# UVLO_MODULE_TOP.net
KiCad netlist of a schematic drawn in Altium Designer
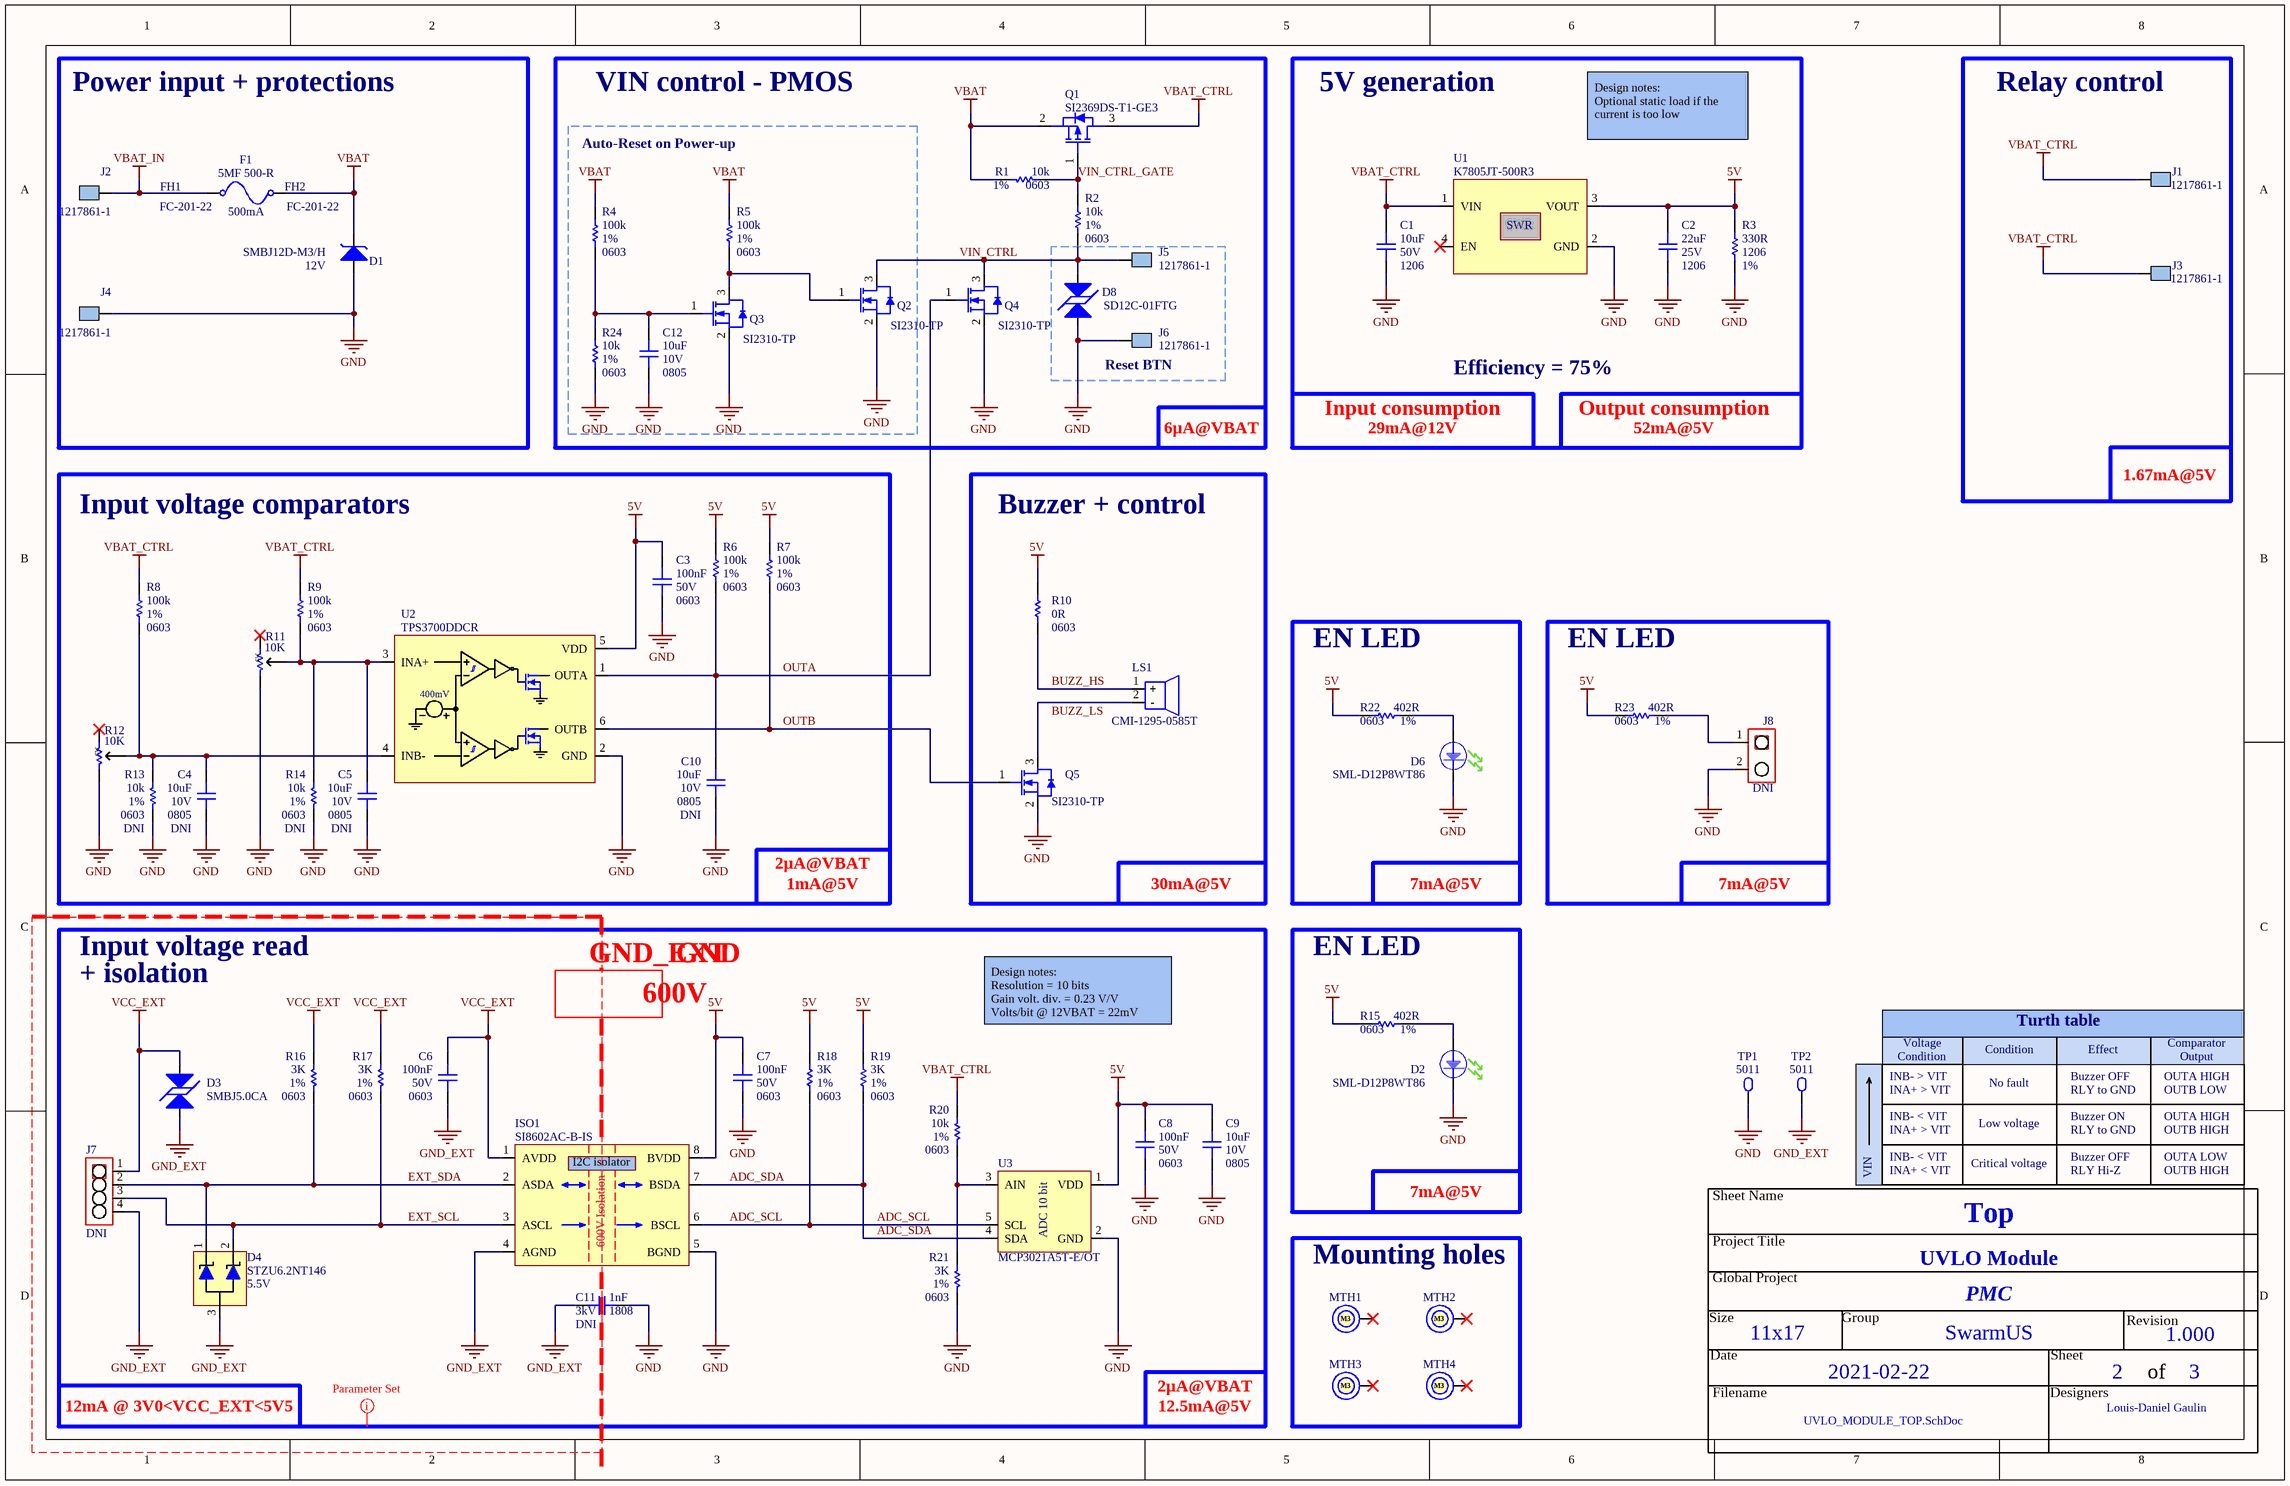
[diagram p0: UVLO_MODULE_TOP.SchDoc]

(export (version "E")
  (design (tool "Eeschema 10.0.6"))
  (components
    (comp (ref "C1")
      (value "10uF")
      (footprint "CAP_CER_1206")
      (description "CAP - CER 10UF 10% 50V X5R - 1206")
      (fields
        (field (name "TOLERANCE") "10%")
        (field (name "PACKAGE") "1206")
        (field (name "VOLTAGE RATING") "50V")
        (field (name "Comment") "GRT31CR61H106KE01L")
        (field (name "CREATEDBY/DATE") "Nicolas Roy - 2018/12/19")
        (field (name "VERIFIEDBY") "Nicolas V. (2019-01-22)")
      )
      (libsource (lib "GRAMS_MASTER_LIB") (part "CAP_CER_GRT31CR61H106KE01L"))
    )
    (comp (ref "C2")
      (value "22uF")
      (footprint "CAP_CER_1206")
      (description "CAP - CER 22uF 10% 25V X5R - 1206")
      (fields
        (field (name "TOLERANCE") "10%")
        (field (name "PACKAGE") "1206")
        (field (name "VOLTAGE RATING") "25V")
        (field (name "Comment") "CL31A226KAHNNNE")
        (field (name "CREATEDBY/DATE") "Philippe Arsenault/21 Janvier 2020")
        (field (name "VERIFIEDBY") "C.Paulin - 28/01/2020")
      )
      (libsource (lib "GRAMS_MASTER_LIB") (part "CAP_CER_CL31A226KAHNNNE"))
    )
    (comp (ref "C3")
      (value "100nF")
      (footprint "CAP_CER_0603")
      (description "CAP - CER 100nF 50V X7R - 0603")
      (fields
        (field (name "TOLERANCE") "10%")
        (field (name "PACKAGE") "0603")
        (field (name "VOLTAGE RATING") "50V")
        (field (name "Comment") "CC0603KRX7R9BB104")
        (field (name "CREATEDBY/DATE") "Louis-Daniel Gaulin / 25-02-2021")
        (field (name "VERIFIEDBY") "Hubert Dube - 26/02/2021")
      )
      (libsource (lib "SWARMUS_LIB") (part "CAP_CER_CC0603KRX7R9BB104"))
    )
    (comp (ref "C4")
      (value "10uF")
      (footprint "CAP_CER_0805")
      (description "CAP - CER 10UF 10% 10V X5R - 0805")
      (fields
        (field (name "TOLERANCE") "10%")
        (field (name "ASSEMBLY NOTE") "DNI")
        (field (name "PACKAGE") "0805")
        (field (name "VOLTAGE RATING") "10V")
        (field (name "Comment") "LMK212BJ106KG-T")
        (field (name "CREATEDBY/DATE") "Caroline Paulin / 25 juillet 2018")
        (field (name "VERIFIEDBY") "Nicolas V. (2019-01-22)")
      )
      (libsource (lib "GRAMS_MASTER_LIB") (part "CAP_CER_LMK212BJ106KG-T"))
    )
    (comp (ref "C5")
      (value "10uF")
      (footprint "CAP_CER_0805")
      (description "CAP - CER 10UF 10% 10V X5R - 0805")
      (fields
        (field (name "TOLERANCE") "10%")
        (field (name "ASSEMBLY NOTE") "DNI")
        (field (name "PACKAGE") "0805")
        (field (name "VOLTAGE RATING") "10V")
        (field (name "Comment") "LMK212BJ106KG-T")
        (field (name "CREATEDBY/DATE") "Caroline Paulin / 25 juillet 2018")
        (field (name "VERIFIEDBY") "Nicolas V. (2019-01-22)")
      )
      (libsource (lib "GRAMS_MASTER_LIB") (part "CAP_CER_LMK212BJ106KG-T"))
    )
    (comp (ref "C6")
      (value "100nF")
      (footprint "CAP_CER_0603")
      (description "CAP - CER 100nF 50V X7R - 0603")
      (fields
        (field (name "TOLERANCE") "10%")
        (field (name "PACKAGE") "0603")
        (field (name "VOLTAGE RATING") "50V")
        (field (name "Comment") "CC0603KRX7R9BB104")
        (field (name "CREATEDBY/DATE") "Louis-Daniel Gaulin / 25-02-2021")
        (field (name "VERIFIEDBY") "Hubert Dube - 26/02/2021")
      )
      (libsource (lib "SWARMUS_LIB") (part "CAP_CER_CC0603KRX7R9BB104"))
    )
    (comp (ref "C7")
      (value "100nF")
      (footprint "CAP_CER_0603")
      (description "CAP - CER 100nF 50V X7R - 0603")
      (fields
        (field (name "TOLERANCE") "10%")
        (field (name "PACKAGE") "0603")
        (field (name "VOLTAGE RATING") "50V")
        (field (name "Comment") "CC0603KRX7R9BB104")
        (field (name "CREATEDBY/DATE") "Louis-Daniel Gaulin / 25-02-2021")
        (field (name "VERIFIEDBY") "Hubert Dube - 26/02/2021")
      )
      (libsource (lib "SWARMUS_LIB") (part "CAP_CER_CC0603KRX7R9BB104"))
    )
    (comp (ref "C8")
      (value "100nF")
      (footprint "CAP_CER_0603")
      (description "CAP - CER 100nF 50V X7R - 0603")
      (fields
        (field (name "TOLERANCE") "10%")
        (field (name "PACKAGE") "0603")
        (field (name "VOLTAGE RATING") "50V")
        (field (name "Comment") "CC0603KRX7R9BB104")
        (field (name "CREATEDBY/DATE") "Louis-Daniel Gaulin / 25-02-2021")
        (field (name "VERIFIEDBY") "Hubert Dube - 26/02/2021")
      )
      (libsource (lib "SWARMUS_LIB") (part "CAP_CER_CC0603KRX7R9BB104"))
    )
    (comp (ref "C9")
      (value "10uF")
      (footprint "CAP_CER_0805")
      (description "CAP - CER 10UF 10% 10V X5R - 0805")
      (fields
        (field (name "TOLERANCE") "10%")
        (field (name "PACKAGE") "0805")
        (field (name "VOLTAGE RATING") "10V")
        (field (name "Comment") "LMK212BJ106KG-T")
        (field (name "CREATEDBY/DATE") "Caroline Paulin / 25 juillet 2018")
        (field (name "VERIFIEDBY") "Nicolas V. (2019-01-22)")
      )
      (libsource (lib "GRAMS_MASTER_LIB") (part "CAP_CER_LMK212BJ106KG-T"))
    )
    (comp (ref "C10")
      (value "10uF")
      (footprint "CAP_CER_0805")
      (description "CAP - CER 10UF 10% 10V X5R - 0805")
      (fields
        (field (name "TOLERANCE") "10%")
        (field (name "ASSEMBLY NOTE") "DNI")
        (field (name "PACKAGE") "0805")
        (field (name "VOLTAGE RATING") "10V")
        (field (name "Comment") "LMK212BJ106KG-T")
        (field (name "CREATEDBY/DATE") "Caroline Paulin / 25 juillet 2018")
        (field (name "VERIFIEDBY") "Nicolas V. (2019-01-22)")
      )
      (libsource (lib "GRAMS_MASTER_LIB") (part "CAP_CER_LMK212BJ106KG-T"))
    )
    (comp (ref "C11")
      (value "1nF")
      (footprint "CAP_CER_1808")
      (description "CAP - CER 1nF 10% 3kV X7R - 1808")
      (fields
        (field (name "TOLERANCE") "10%")
        (field (name "ASSEMBLY NOTE") "DNI")
        (field (name "PACKAGE") "1808")
        (field (name "VOLTAGE RATING") "3kV")
        (field (name "Comment") "1808HC102KAT1A")
        (field (name "CREATEDBY/DATE") "Joel Lemay 2018-08-29")
        (field (name "VERIFIEDBY") "Caroline Paulin - 7 sept 2018")
      )
      (libsource (lib "GRAMS_MASTER_LIB") (part "CAP_CER_1808HC102KAT1A"))
    )
    (comp (ref "C12")
      (value "10uF")
      (footprint "CAP_CER_0805")
      (description "CAP - CER 10UF 10% 10V X5R - 0805")
      (fields
        (field (name "TOLERANCE") "10%")
        (field (name "PACKAGE") "0805")
        (field (name "VOLTAGE RATING") "10V")
        (field (name "Comment") "LMK212BJ106KG-T")
        (field (name "CREATEDBY/DATE") "Caroline Paulin / 25 juillet 2018")
        (field (name "VERIFIEDBY") "Nicolas V. (2019-01-22)")
      )
      (libsource (lib "GRAMS_MASTER_LIB") (part "CAP_CER_LMK212BJ106KG-T"))
    )
    (comp (ref "D1")
      (value "SMBJ12D-M3/H")
      (footprint "TVS_SMBJ12D-M3/H")
      (description "TVS - DIODE 12V 19.6V - DO-214AA")
      (fields
        (field (name "ALTIUM_VALUE") "12V")
        (field (name "CREATEDBY/DATE") "Joel Lemay 2019-04-17")
        (field (name "VERIFIEDBY") "C.Paulin 6/02/2020")
      )
      (libsource (lib "GRAMS_MASTER_LIB") (part "TVS_SMBJ12D-M3/H"))
    )
    (comp (ref "D2")
      (value "SML-D12P8WT86")
      (footprint "LED_SML-D12P8WT86")
      (description "LED - GREEN DIFFUSED 0603 SMD - 0603")
      (fields
        (field (name "CREATEDBY/DATE") "Keven Deslandes - 2018/11/21")
        (field (name "VERIFIEDBY") "Caroline Paulin - 13 février 2019")
      )
      (libsource (lib "GRAMS_MASTER_LIB") (part "LED_SML-D12P8WT86"))
    )
    (comp (ref "D3")
      (value "SMBJ5.0CA")
      (footprint "TVS_PWR_SMBJ5.0CA")
      (description "TVS - BIDIR 5V 9.2V 600W - DO214AA")
      (fields
        (field (name "CREATEDBY/DATE") "Jonathan Bouchard - 2019-03-22")
        (field (name "VERIFIEDBY") "Nicolas V. (2019-05-06)")
      )
      (libsource (lib "GRAMS_MASTER_LIB") (part "TVS_PWR_SMBJ5.0CA"))
    )
    (comp (ref "D4")
      (value "STZU6.2NT146")
      (footprint "TVS_DATA_STZU6.2NT146")
      (description "TVS - TVS DIODE 5.5V 5.9V - SOT-23-3")
      (fields
        (field (name "VOLTAGE RATING") "5.5V")
        (field (name "CREATEDBY/DATE") "Louis-Daniel Gaulin / 02-03-2021")
        (field (name "VERIFIEDBY") "Philippe Arsenault / 02-03-2021")
      )
      (libsource (lib "SWARMUS_LIB") (part "TVS_DATA_STZU6.2NT146"))
    )
    (comp (ref "D6")
      (value "SML-D12P8WT86")
      (footprint "LED_SML-D12P8WT86")
      (description "LED - GREEN DIFFUSED 0603 SMD - 0603")
      (fields
        (field (name "CREATEDBY/DATE") "Keven Deslandes - 2018/11/21")
        (field (name "VERIFIEDBY") "Caroline Paulin - 13 février 2019")
      )
      (libsource (lib "GRAMS_MASTER_LIB") (part "LED_SML-D12P8WT86"))
    )
    (comp (ref "D8")
      (value "SD12C-01FTG")
      (footprint "TVS_DATA_SD12C-01FTG")
      (description "TVS - BIDIR 12V 450W - SOD-323")
      (fields
        (field (name "CREATEDBY/DATE") "O.D.Frenette - 2020-09-01")
        (field (name "VERIFIEDBY") "C.Paulin - 2020-09-09")
      )
      (libsource (lib "GRAMS_MASTER_LIB") (part "TVS_DATA_SD12C-01FTG"))
    )
    (comp (ref "F1")
      (value "5MF 500-R")
      (footprint "FUS_5MF 500-R")
      (description "FUS - CARTRIDGE GLASS 500mA 250VAC/125VDC - 5X20mm")
      (fields
        (field (name "CURRENT RATING") "500mA")
        (field (name "CREATEDBY/DATE") "Louis-Daniel Gaulin")
        (field (name "VERIFIEDBY") "Hubert Dube - 26/02/2021")
      )
      (libsource (lib "SWARMUS_LIB") (part "FUS_5MF 500-R"))
    )
    (comp (ref "FH1")
      (value "FC-201-22")
      (footprint "FHO_FC-201-22")
      (description "FHO - FUSE CLIP 5mm CARTRIDGE 10A PCB - 2-TH")
      (fields
        (field (name "CREATEDBY/DATE") "Louis-Daniel Gaulin / 26-02-2021")
        (field (name "VERIFIEDBY") "Hubert Dube - 26/02/2021")
      )
      (libsource (lib "SWARMUS_LIB") (part "FHO_FC-201-22"))
    )
    (comp (ref "FH2")
      (value "FC-201-22")
      (footprint "FHO_FC-201-22")
      (description "FHO - FUSE CLIP 5mm CARTRIDGE 10A PCB - 2-TH")
      (fields
        (field (name "CREATEDBY/DATE") "Louis-Daniel Gaulin / 26-02-2021")
        (field (name "VERIFIEDBY") "Hubert Dube - 26/02/2021")
      )
      (libsource (lib "SWARMUS_LIB") (part "FHO_FC-201-22"))
    )
    (comp (ref "ISO1")
      (value "SI8602AC-B-IS")
      (footprint "ISO_SI8602AC-B-IS")
      (description "ISO - DGTL ISO 600V 2CH I2C  - 8-SOIC")
      (fields
        (field (name "CREATEDBY/DATE") "Louis-Daniel Gaulin / 25-02-2021")
        (field (name "VERIFIEDBY") "Hubert Dube - 26/02/2021")
      )
      (libsource (lib "SWARMUS_LIB") (part "ISO_SI8602AC-B-IS"))
    )
    (comp (ref "J1")
      (value "1217861-1")
      (footprint "CON_1217861-1")
      (description "CON - Quick connect tab - TH")
      (fields
        (field (name "CREATEDBY/DATE") "Louis-Daniel Gaulin / 24-02-2021")
        (field (name "VERIFIEDBY") "Hubert Dube - 26/02/2021")
      )
      (libsource (lib "") (part "CON_1217861-1_1"))
    )
    (comp (ref "J2")
      (value "1217861-1")
      (footprint "CON_1217861-1")
      (description "CON - Quick connect tab - TH")
      (fields
        (field (name "CREATEDBY/DATE") "Louis-Daniel Gaulin / 24-02-2021")
        (field (name "VERIFIEDBY") "Hubert Dube - 26/02/2021")
      )
      (libsource (lib "SWARMUS_LIB") (part "CON_1217861-1"))
    )
    (comp (ref "J3")
      (value "1217861-1")
      (footprint "CON_1217861-1")
      (description "CON - Quick connect tab - TH")
      (fields
        (field (name "CREATEDBY/DATE") "Louis-Daniel Gaulin / 24-02-2021")
        (field (name "VERIFIEDBY") "Hubert Dube - 26/02/2021")
      )
      (libsource (lib "") (part "CON_1217861-1_1"))
    )
    (comp (ref "J4")
      (value "1217861-1")
      (footprint "CON_1217861-1")
      (description "CON - Quick connect tab - TH")
      (fields
        (field (name "CREATEDBY/DATE") "Louis-Daniel Gaulin / 24-02-2021")
        (field (name "VERIFIEDBY") "Hubert Dube - 26/02/2021")
      )
      (libsource (lib "SWARMUS_LIB") (part "CON_1217861-1"))
    )
    (comp (ref "J5")
      (value "1217861-1")
      (footprint "CON_1217861-1")
      (description "CON - Quick connect tab - TH")
      (fields
        (field (name "CREATEDBY/DATE") "Louis-Daniel Gaulin / 24-02-2021")
        (field (name "VERIFIEDBY") "Hubert Dube - 26/02/2021")
      )
      (libsource (lib "") (part "CON_1217861-1_2"))
    )
    (comp (ref "J6")
      (value "1217861-1")
      (footprint "CON_1217861-1")
      (description "CON - Quick connect tab - TH")
      (fields
        (field (name "CREATEDBY/DATE") "Louis-Daniel Gaulin / 24-02-2021")
        (field (name "VERIFIEDBY") "Hubert Dube - 26/02/2021")
      )
      (libsource (lib "") (part "CON_1217861-1_2"))
    )
    (comp (ref "J7")
      (value "CON_HDR_1X4")
      (footprint "CON_HDR_1X4")
      (description "CON - Header 1X4 pins, 100Mils - TH-4")
      (fields
        (field (name "ASSEMBLY NOTE") "DNI")
        (field (name "CREATEDBY/DATE") "Nicolas V (2020-02-24)")
        (field (name "VERIFIEDBY") "Nicolas V (2020-02-24)")
      )
      (libsource (lib "GRAMS_MASTER_LIB") (part "CON_HDR_1X4"))
    )
    (comp (ref "J8")
      (value "CON_HDR_1X2")
      (footprint "CON_HDR_1X2")
      (description "CON - Header 1x2 pins 100 mil -TH")
      (fields
        (field (name "ASSEMBLY NOTE") "DNI")
        (field (name "CREATEDBY/DATE") "Nicolas Roy/2 dec 2016")
        (field (name "VERIFIEDBY") "Caroline Paulin / 10 juillet 2018")
      )
      (libsource (lib "GRAMS_MASTER_LIB") (part "CON_HDR_1X2"))
    )
    (comp (ref "LS1")
      (value "CMI-1295-0585T")
      (footprint "UND_SPK_CMI-1295-0585T")
      (description "LS - Buzzer indicator 5V 30mA 2.3kHz 85dB - TH")
      (fields
        (field (name "CREATEDBY/DATE") "Louis-Daniel Gaulin / 24-02-2021")
        (field (name "VERIFIEDBY") "Hubert Dube - 26/02/2021")
      )
      (libsource (lib "SWARMUS_LIB") (part "UND_LS_CMI-1295-0585T"))
    )
    (comp (ref "MTH1")
      (value "M3")
      (footprint "MTH_M3")
      (description "MTH - MOUNTING HOLE M3 PLATED - M3")
      (fields
        (field (name "CREATEDBY/DATE") "Jonathan Bouchard 2018-07-23")
        (field (name "VERIFIEDBY") "Arnaud Samson 23-07-18")
      )
      (libsource (lib "GRAMS_MASTER_LIB") (part "MTH_M3"))
    )
    (comp (ref "MTH2")
      (value "M3")
      (footprint "MTH_M3")
      (description "MTH - MOUNTING HOLE M3 PLATED - M3")
      (fields
        (field (name "CREATEDBY/DATE") "Jonathan Bouchard 2018-07-23")
        (field (name "VERIFIEDBY") "Arnaud Samson 23-07-18")
      )
      (libsource (lib "GRAMS_MASTER_LIB") (part "MTH_M3"))
    )
    (comp (ref "MTH3")
      (value "M3")
      (footprint "MTH_M3")
      (description "MTH - MOUNTING HOLE M3 PLATED - M3")
      (fields
        (field (name "CREATEDBY/DATE") "Jonathan Bouchard 2018-07-23")
        (field (name "VERIFIEDBY") "Arnaud Samson 23-07-18")
      )
      (libsource (lib "GRAMS_MASTER_LIB") (part "MTH_M3"))
    )
    (comp (ref "MTH4")
      (value "M3")
      (footprint "MTH_M3")
      (description "MTH - MOUNTING HOLE M3 PLATED - M3")
      (fields
        (field (name "CREATEDBY/DATE") "Jonathan Bouchard 2018-07-23")
        (field (name "VERIFIEDBY") "Arnaud Samson 23-07-18")
      )
      (libsource (lib "GRAMS_MASTER_LIB") (part "MTH_M3"))
    )
    (comp (ref "Q1")
      (value "SI2369DS-T1-GE3")
      (footprint "TRX_PMOS_SI2369DS-T1-GE3")
      (description "TRX - PMOS 30V 7.6A - SOT−23")
      (fields
        (field (name "CREATEDBY/DATE") "Louis-Daniel Gaulin / 30-07-2020")
        (field (name "VERIFIEDBY") "Philippe Arsenault/2020-11-06")
      )
      (libsource (lib "SWARMUS_LIB") (part "TRX_PMOS_SI2369DS-T1-GE3"))
    )
    (comp (ref "Q2")
      (value "SI2310-TP")
      (footprint "TRX_NMOS_SI2310-TP")
      (description "TRX - MOSFET N-CH 60V 3A - SOT-23")
      (fields
        (field (name "CREATEDBY/DATE") "Louis-Daniel Gaulin / 20-02-2020")
        (field (name "VERIFIEDBY") "C.Paulin - 21/02/2020")
      )
      (libsource (lib "GRAMS_MASTER_LIB") (part "TRX_NMOS_SI2310-TP"))
    )
    (comp (ref "Q3")
      (value "SI2310-TP")
      (footprint "TRX_NMOS_SI2310-TP")
      (description "TRX - MOSFET N-CH 60V 3A - SOT-23")
      (fields
        (field (name "CREATEDBY/DATE") "Louis-Daniel Gaulin / 20-02-2020")
        (field (name "VERIFIEDBY") "C.Paulin - 21/02/2020")
      )
      (libsource (lib "GRAMS_MASTER_LIB") (part "TRX_NMOS_SI2310-TP"))
    )
    (comp (ref "Q4")
      (value "SI2310-TP")
      (footprint "TRX_NMOS_SI2310-TP")
      (description "TRX - MOSFET N-CH 60V 3A - SOT-23")
      (fields
        (field (name "CREATEDBY/DATE") "Louis-Daniel Gaulin / 20-02-2020")
        (field (name "VERIFIEDBY") "C.Paulin - 21/02/2020")
      )
      (libsource (lib "GRAMS_MASTER_LIB") (part "TRX_NMOS_SI2310-TP"))
    )
    (comp (ref "Q5")
      (value "SI2310-TP")
      (footprint "TRX_NMOS_SI2310-TP")
      (description "TRX - MOSFET N-CH 60V 3A - SOT-23")
      (fields
        (field (name "CREATEDBY/DATE") "Louis-Daniel Gaulin / 20-02-2020")
        (field (name "VERIFIEDBY") "C.Paulin - 21/02/2020")
      )
      (libsource (lib "GRAMS_MASTER_LIB") (part "TRX_NMOS_SI2310-TP"))
    )
    (comp (ref "R1")
      (value "10k")
      (footprint "RES_0603")
      (description "RES - 10k 1% 1/10W - 0603")
      (fields
        (field (name "TOLERANCE") "1%")
        (field (name "PACKAGE") "0603")
        (field (name "Comment") "RC0603FR-0710KL")
        (field (name "CREATEDBY/DATE") "Louis-Daniel Gaulin / 24-02-2021")
        (field (name "VERIFIEDBY") "Hubert Dube - 26/02/2021")
      )
      (libsource (lib "SWARMUS_LIB") (part "RES_RC0603FR-0710KL"))
    )
    (comp (ref "R2")
      (value "10k")
      (footprint "RES_0603")
      (description "RES - 10k 1% 1/10W - 0603")
      (fields
        (field (name "TOLERANCE") "1%")
        (field (name "PACKAGE") "0603")
        (field (name "Comment") "RC0603FR-0710KL")
        (field (name "CREATEDBY/DATE") "Louis-Daniel Gaulin / 24-02-2021")
        (field (name "VERIFIEDBY") "Hubert Dube - 26/02/2021")
      )
      (libsource (lib "SWARMUS_LIB") (part "RES_RC0603FR-0710KL"))
    )
    (comp (ref "R3")
      (value "330R")
      (footprint "RES_1206")
      (description "RES - 330 OHM 1% 1/4W - 1206")
      (fields
        (field (name "TOLERANCE") "1%")
        (field (name "PACKAGE") "1206")
        (field (name "Comment") "RC1206FR-07330RL")
        (field (name "CREATEDBY/DATE") "Nicolas V. (2019-11-19)")
        (field (name "VERIFIEDBY") "Nicolas V. (2019-11-19)")
      )
      (libsource (lib "GRAMS_MASTER_LIB") (part "RES_RC1206FR-07330RL"))
    )
    (comp (ref "R4")
      (value "100k")
      (footprint "RES_0603")
      (description "RES - 100k 1% 1/10W - 0603")
      (fields
        (field (name "TOLERANCE") "1%")
        (field (name "PACKAGE") "0603")
        (field (name "Comment") "RC0603FR-07100KL")
        (field (name "CREATEDBY/DATE") "Louis-Daniel Gaulin / 24-02-2021")
        (field (name "VERIFIEDBY") "Hubert Dube")
      )
      (libsource (lib "SWARMUS_LIB") (part "RES_RC0603FR-07100KL"))
    )
    (comp (ref "R5")
      (value "100k")
      (footprint "RES_0603")
      (description "RES - 100k 1% 1/10W - 0603")
      (fields
        (field (name "TOLERANCE") "1%")
        (field (name "PACKAGE") "0603")
        (field (name "Comment") "RC0603FR-07100KL")
        (field (name "CREATEDBY/DATE") "Louis-Daniel Gaulin / 24-02-2021")
        (field (name "VERIFIEDBY") "Hubert Dube")
      )
      (libsource (lib "SWARMUS_LIB") (part "RES_RC0603FR-07100KL"))
    )
    (comp (ref "R6")
      (value "100k")
      (footprint "RES_0603")
      (description "RES - 100k 1% 1/10W - 0603")
      (fields
        (field (name "TOLERANCE") "1%")
        (field (name "PACKAGE") "0603")
        (field (name "Comment") "RC0603FR-07100KL")
        (field (name "CREATEDBY/DATE") "Louis-Daniel Gaulin / 24-02-2021")
        (field (name "VERIFIEDBY") "Hubert Dube")
      )
      (libsource (lib "SWARMUS_LIB") (part "RES_RC0603FR-07100KL"))
    )
    (comp (ref "R7")
      (value "100k")
      (footprint "RES_0603")
      (description "RES - 100k 1% 1/10W - 0603")
      (fields
        (field (name "TOLERANCE") "1%")
        (field (name "PACKAGE") "0603")
        (field (name "Comment") "RC0603FR-07100KL")
        (field (name "CREATEDBY/DATE") "Louis-Daniel Gaulin / 24-02-2021")
        (field (name "VERIFIEDBY") "Hubert Dube")
      )
      (libsource (lib "SWARMUS_LIB") (part "RES_RC0603FR-07100KL"))
    )
    (comp (ref "R8")
      (value "100k")
      (footprint "RES_0603")
      (description "RES - 100k 1% 1/10W - 0603")
      (fields
        (field (name "TOLERANCE") "1%")
        (field (name "PACKAGE") "0603")
        (field (name "Comment") "RC0603FR-07100KL")
        (field (name "CREATEDBY/DATE") "Louis-Daniel Gaulin / 24-02-2021")
        (field (name "VERIFIEDBY") "Hubert Dube")
      )
      (libsource (lib "SWARMUS_LIB") (part "RES_RC0603FR-07100KL"))
    )
    (comp (ref "R9")
      (value "100k")
      (footprint "RES_0603")
      (description "RES - 100k 1% 1/10W - 0603")
      (fields
        (field (name "TOLERANCE") "1%")
        (field (name "PACKAGE") "0603")
        (field (name "Comment") "RC0603FR-07100KL")
        (field (name "CREATEDBY/DATE") "Louis-Daniel Gaulin / 24-02-2021")
        (field (name "VERIFIEDBY") "Hubert Dube")
      )
      (libsource (lib "SWARMUS_LIB") (part "RES_RC0603FR-07100KL"))
    )
    (comp (ref "R10")
      (value "0R")
      (footprint "RES_0603")
      (description "RES - 0 ohm jumper 1/10W - 0603")
      (fields
        (field (name "PACKAGE") "0603")
        (field (name "Comment") "RC0603JR-070RL")
        (field (name "CREATEDBY/DATE") "L-P Gauthier 2018-10-30")
        (field (name "VERIFIEDBY") "Caroline Paulin  - 5/11/2018")
      )
      (libsource (lib "GRAMS_MASTER_LIB") (part "RES_RC0603JR-070RL"))
    )
    (comp (ref "R11")
      (value "10K")
      (footprint "POT_3362P-1-103LF")
      (description "RES -  POT 10K 1/2W LINEAR PLASTIC 1 turn - TH")
      (fields
        (field (name "TOLERANCE") "10%")
        (field (name "Comment") "3362P-1-103LF")
        (field (name "CREATEDBY/DATE") "Louis-Daniel Gaulin / 24-02-2021")
        (field (name "VERIFIEDBY") "Hubert Dube - 26/02/2021")
      )
      (libsource (lib "SWARMUS_LIB") (part "POT_3362P-1-103LF"))
    )
    (comp (ref "R12")
      (value "10K")
      (footprint "POT_3362P-1-103LF")
      (description "RES -  POT 10K 1/2W LINEAR PLASTIC 1 turn - TH")
      (fields
        (field (name "TOLERANCE") "10%")
        (field (name "Comment") "3362P-1-103LF")
        (field (name "CREATEDBY/DATE") "Louis-Daniel Gaulin / 24-02-2021")
        (field (name "VERIFIEDBY") "Hubert Dube - 26/02/2021")
      )
      (libsource (lib "SWARMUS_LIB") (part "POT_3362P-1-103LF"))
    )
    (comp (ref "R13")
      (value "10k")
      (footprint "RES_0603")
      (description "RES - 10k 1% 1/10W - 0603")
      (fields
        (field (name "ASSEMBLY NOTE") "DNI")
        (field (name "TOLERANCE") "1%")
        (field (name "PACKAGE") "0603")
        (field (name "Comment") "RC0603FR-0710KL")
        (field (name "CREATEDBY/DATE") "Louis-Daniel Gaulin / 24-02-2021")
        (field (name "VERIFIEDBY") "Hubert Dube - 26/02/2021")
      )
      (libsource (lib "SWARMUS_LIB") (part "RES_RC0603FR-0710KL"))
    )
    (comp (ref "R14")
      (value "10k")
      (footprint "RES_0603")
      (description "RES - 10k 1% 1/10W - 0603")
      (fields
        (field (name "ASSEMBLY NOTE") "DNI")
        (field (name "TOLERANCE") "1%")
        (field (name "PACKAGE") "0603")
        (field (name "Comment") "RC0603FR-0710KL")
        (field (name "CREATEDBY/DATE") "Louis-Daniel Gaulin / 24-02-2021")
        (field (name "VERIFIEDBY") "Hubert Dube - 26/02/2021")
      )
      (libsource (lib "SWARMUS_LIB") (part "RES_RC0603FR-0710KL"))
    )
    (comp (ref "R15")
      (value "402R")
      (footprint "RES_0603")
      (description "RES - 402R 1% 1/10W - 0603")
      (fields
        (field (name "TOLERANCE") "1%")
        (field (name "PACKAGE") "0603")
        (field (name "Comment") "RC0603FR-07402RL")
        (field (name "CREATEDBY/DATE") "Louis-Daniel Gaulin / 24-02-2021")
        (field (name "VERIFIEDBY") "Hubert Dube - 26/02/2021")
      )
      (libsource (lib "SWARMUS_LIB") (part "RES_RC0603FR-07402RL"))
    )
    (comp (ref "R16")
      (value "3K")
      (footprint "RES_0603")
      (description "RES - 3k 1% 1/10W - 0603")
      (fields
        (field (name "TOLERANCE") "1%")
        (field (name "PACKAGE") "0603")
        (field (name "Comment") "RC0603FR-073KL")
        (field (name "CREATEDBY/DATE") "Louis-Daniel Gaulin / 24-02-2021")
        (field (name "VERIFIEDBY") "Hubert Dube - 26/02/2021")
      )
      (libsource (lib "SWARMUS_LIB") (part "RES_RC0603FR-073KL"))
    )
    (comp (ref "R17")
      (value "3K")
      (footprint "RES_0603")
      (description "RES - 3k 1% 1/10W - 0603")
      (fields
        (field (name "TOLERANCE") "1%")
        (field (name "PACKAGE") "0603")
        (field (name "Comment") "RC0603FR-073KL")
        (field (name "CREATEDBY/DATE") "Louis-Daniel Gaulin / 24-02-2021")
        (field (name "VERIFIEDBY") "Hubert Dube - 26/02/2021")
      )
      (libsource (lib "SWARMUS_LIB") (part "RES_RC0603FR-073KL"))
    )
    (comp (ref "R18")
      (value "3K")
      (footprint "RES_0603")
      (description "RES - 3k 1% 1/10W - 0603")
      (fields
        (field (name "TOLERANCE") "1%")
        (field (name "PACKAGE") "0603")
        (field (name "Comment") "RC0603FR-073KL")
        (field (name "CREATEDBY/DATE") "Louis-Daniel Gaulin / 24-02-2021")
        (field (name "VERIFIEDBY") "Hubert Dube - 26/02/2021")
      )
      (libsource (lib "SWARMUS_LIB") (part "RES_RC0603FR-073KL"))
    )
    (comp (ref "R19")
      (value "3K")
      (footprint "RES_0603")
      (description "RES - 3k 1% 1/10W - 0603")
      (fields
        (field (name "TOLERANCE") "1%")
        (field (name "PACKAGE") "0603")
        (field (name "Comment") "RC0603FR-073KL")
        (field (name "CREATEDBY/DATE") "Louis-Daniel Gaulin / 24-02-2021")
        (field (name "VERIFIEDBY") "Hubert Dube - 26/02/2021")
      )
      (libsource (lib "SWARMUS_LIB") (part "RES_RC0603FR-073KL"))
    )
    (comp (ref "R20")
      (value "10k")
      (footprint "RES_0603")
      (description "RES - 10k 1% 1/10W - 0603")
      (fields
        (field (name "TOLERANCE") "1%")
        (field (name "PACKAGE") "0603")
        (field (name "Comment") "RC0603FR-0710KL")
        (field (name "CREATEDBY/DATE") "Louis-Daniel Gaulin / 24-02-2021")
        (field (name "VERIFIEDBY") "Hubert Dube - 26/02/2021")
      )
      (libsource (lib "SWARMUS_LIB") (part "RES_RC0603FR-0710KL"))
    )
    (comp (ref "R21")
      (value "3K")
      (footprint "RES_0603")
      (description "RES - 3k 1% 1/10W - 0603")
      (fields
        (field (name "TOLERANCE") "1%")
        (field (name "PACKAGE") "0603")
        (field (name "Comment") "RC0603FR-073KL")
        (field (name "CREATEDBY/DATE") "Louis-Daniel Gaulin / 24-02-2021")
        (field (name "VERIFIEDBY") "Hubert Dube - 26/02/2021")
      )
      (libsource (lib "SWARMUS_LIB") (part "RES_RC0603FR-073KL"))
    )
    (comp (ref "R22")
      (value "402R")
      (footprint "RES_0603")
      (description "RES - 402R 1% 1/10W - 0603")
      (fields
        (field (name "TOLERANCE") "1%")
        (field (name "PACKAGE") "0603")
        (field (name "Comment") "RC0603FR-07402RL")
        (field (name "CREATEDBY/DATE") "Louis-Daniel Gaulin / 24-02-2021")
        (field (name "VERIFIEDBY") "Hubert Dube - 26/02/2021")
      )
      (libsource (lib "SWARMUS_LIB") (part "RES_RC0603FR-07402RL"))
    )
    (comp (ref "R23")
      (value "402R")
      (footprint "RES_0603")
      (description "RES - 402R 1% 1/10W - 0603")
      (fields
        (field (name "TOLERANCE") "1%")
        (field (name "PACKAGE") "0603")
        (field (name "Comment") "RC0603FR-07402RL")
        (field (name "CREATEDBY/DATE") "Louis-Daniel Gaulin / 24-02-2021")
        (field (name "VERIFIEDBY") "Hubert Dube - 26/02/2021")
      )
      (libsource (lib "SWARMUS_LIB") (part "RES_RC0603FR-07402RL"))
    )
    (comp (ref "R24")
      (value "10k")
      (footprint "RES_0603")
      (description "RES - 10k 1% 1/10W - 0603")
      (fields
        (field (name "TOLERANCE") "1%")
        (field (name "PACKAGE") "0603")
        (field (name "Comment") "RC0603FR-0710KL")
        (field (name "CREATEDBY/DATE") "Louis-Daniel Gaulin / 24-02-2021")
        (field (name "VERIFIEDBY") "Hubert Dube - 26/02/2021")
      )
      (libsource (lib "SWARMUS_LIB") (part "RES_RC0603FR-0710KL"))
    )
    (comp (ref "TP1")
      (value "5011")
      (footprint "TPO_5011")
      (description "TPO - TEST POINT - TH")
      (fields
        (field (name "CREATEDBY/DATE") "Louis-Daniel Gauli / 02-11-2020")
        (field (name "VERIFIEDBY") "Philippe Arsenault/2020-11-06")
      )
      (libsource (lib "SWARMUS_LIB") (part "TPO_5011"))
    )
    (comp (ref "TP2")
      (value "5011")
      (footprint "TPO_5011")
      (description "TPO - TEST POINT - TH")
      (fields
        (field (name "CREATEDBY/DATE") "Louis-Daniel Gauli / 02-11-2020")
        (field (name "VERIFIEDBY") "Philippe Arsenault/2020-11-06")
      )
      (libsource (lib "SWARMUS_LIB") (part "TPO_5011"))
    )
    (comp (ref "U1")
      (value "K7805JT-500R3")
      (footprint "REG_SWR_K7805JT-500R3")
      (description "REG_DC DC CONVERTER 5V 2.5W - 4-SMD Module")
      (fields
        (field (name "CREATEDBY/DATE") "Louis-Daniel Gaulin / 25-02-2021")
        (field (name "VERIFIEDBY") "Hubert Dube - 26/02/2021")
      )
      (libsource (lib "SWARMUS_LIB") (part "REG_SWR_K7805JT-500R3"))
    )
    (comp (ref "U2")
      (value "TPS3700DDCR")
      (footprint "CMP_TPS3700DDCR")
      (description "CMP - Comparator Window Open Drain - TSOT-23-6")
      (fields
        (field (name "CREATEDBY/DATE") "Louis-Daniel Gaulin / 22-02-2021")
        (field (name "VERIFIEDBY") "Hubert Dube - 26/02/2021")
      )
      (libsource (lib "SWARMUS_LIB") (part "CMP_TPS3700DDCR"))
    )
    (comp (ref "U3")
      (value "MCP3021A5T-E/OT")
      (footprint "ADC_MCP3021A5T-E/OT")
      (description "ADC - IC ADC 10BIT I2C 22.3KSPS - SOT-23-5")
      (fields
        (field (name "CREATEDBY/DATE") "Louis-Daniel Gaulin / 24-02-2021")
        (field (name "VERIFIEDBY") "Hubert Dube - 26/02/2021")
      )
      (libsource (lib "SWARMUS_LIB") (part "ADC_MCP3021A5T-E/OT"))
    )
  )
  (nets
    (net (code "1") (name "/ADC_SCL") (class "Default")
      (node (ref "ISO1") (pin "6") (pinfunction "BSCL_6") (pintype "passive"))
      (node (ref "R18") (pin "1") (pinfunction "1_1") (pintype "passive"))
      (node (ref "U3") (pin "5") (pinfunction "SCL_5") (pintype "passive"))
    )
    (net (code "2") (name "/ADC_SDA") (class "Default")
      (node (ref "ISO1") (pin "7") (pinfunction "BSDA_7") (pintype "passive"))
      (node (ref "R19") (pin "1") (pinfunction "1_1") (pintype "passive"))
      (node (ref "U3") (pin "4") (pinfunction "SDA_4") (pintype "passive"))
    )
    (net (code "3") (name "/BUZZ_HS") (class "Default")
      (node (ref "LS1") (pin "1") (pinfunction "+_1") (pintype "passive"))
      (node (ref "R10") (pin "1") (pinfunction "1_1") (pintype "passive"))
    )
    (net (code "4") (name "/BUZZ_LS") (class "Default")
      (node (ref "LS1") (pin "2") (pinfunction "-_2") (pintype "passive"))
      (node (ref "Q5") (pin "3") (pinfunction "D_3") (pintype "passive"))
    )
    (net (code "5") (name "/EXT_SCL") (class "Default")
      (node (ref "D4") (pin "2") (pinfunction "K2_2") (pintype "passive"))
      (node (ref "ISO1") (pin "3") (pinfunction "ASCL_3") (pintype "passive"))
      (node (ref "J7") (pin "3") (pinfunction "3_3") (pintype "passive"))
      (node (ref "R17") (pin "1") (pinfunction "1_1") (pintype "passive"))
    )
    (net (code "6") (name "/EXT_SDA") (class "Default")
      (node (ref "D4") (pin "1") (pinfunction "K1_1") (pintype "passive"))
      (node (ref "ISO1") (pin "2") (pinfunction "ASDA_2") (pintype "passive"))
      (node (ref "J7") (pin "2") (pinfunction "2_2") (pintype "passive"))
      (node (ref "R16") (pin "1") (pinfunction "1_1") (pintype "passive"))
    )
    (net (code "7") (name "/OUTA") (class "Default")
      (node (ref "C10") (pin "2") (pinfunction "2_2") (pintype "passive"))
      (node (ref "Q4") (pin "1") (pinfunction "G_1") (pintype "passive"))
      (node (ref "R6") (pin "1") (pinfunction "1_1") (pintype "passive"))
      (node (ref "U2") (pin "1") (pinfunction "OUTA_1") (pintype "passive"))
    )
    (net (code "8") (name "/OUTB") (class "Default")
      (node (ref "Q5") (pin "1") (pinfunction "G_1") (pintype "passive"))
      (node (ref "R7") (pin "1") (pinfunction "1_1") (pintype "passive"))
      (node (ref "U2") (pin "6") (pinfunction "OUTB_6") (pintype "passive"))
    )
    (net (code "9") (name "/VIN_CTRL") (class "Default")
      (node (ref "D8") (pin "1") (pinfunction "1_1") (pintype "passive"))
      (node (ref "J5") (pin "1") (pintype "passive"))
      (node (ref "Q2") (pin "3") (pinfunction "D_3") (pintype "passive"))
      (node (ref "Q4") (pin "3") (pinfunction "D_3") (pintype "passive"))
      (node (ref "R2") (pin "1") (pinfunction "1_1") (pintype "passive"))
    )
    (net (code "10") (name "/VIN_CTRL_GATE") (class "Default")
      (node (ref "Q1") (pin "1") (pinfunction "G_1") (pintype "passive"))
      (node (ref "R1") (pin "1") (pinfunction "1_1") (pintype "passive"))
      (node (ref "R2") (pin "2") (pinfunction "2_2") (pintype "passive"))
    )
    (net (code "11") (name "5V") (class "Default")
      (node (ref "C2") (pin "2") (pinfunction "2_2") (pintype "passive"))
      (node (ref "C3") (pin "2") (pinfunction "2_2") (pintype "passive"))
      (node (ref "C7") (pin "2") (pinfunction "2_2") (pintype "passive"))
      (node (ref "C8") (pin "2") (pinfunction "2_2") (pintype "passive"))
      (node (ref "C9") (pin "2") (pinfunction "2_2") (pintype "passive"))
      (node (ref "ISO1") (pin "8") (pinfunction "BVDD_8") (pintype "passive"))
      (node (ref "R10") (pin "2") (pinfunction "2_2") (pintype "passive"))
      (node (ref "R15") (pin "1") (pinfunction "1_1") (pintype "passive"))
      (node (ref "R18") (pin "2") (pinfunction "2_2") (pintype "passive"))
      (node (ref "R19") (pin "2") (pinfunction "2_2") (pintype "passive"))
      (node (ref "R22") (pin "1") (pinfunction "1_1") (pintype "passive"))
      (node (ref "R23") (pin "1") (pinfunction "1_1") (pintype "passive"))
      (node (ref "R3") (pin "2") (pinfunction "2_2") (pintype "passive"))
      (node (ref "R6") (pin "2") (pinfunction "2_2") (pintype "passive"))
      (node (ref "R7") (pin "2") (pinfunction "2_2") (pintype "passive"))
      (node (ref "U1") (pin "3") (pinfunction "VOUT_3") (pintype "passive"))
      (node (ref "U2") (pin "5") (pinfunction "VDD_5") (pintype "passive"))
      (node (ref "U3") (pin "1") (pinfunction "VDD_1") (pintype "passive"))
    )
    (net (code "12") (name "GND") (class "Default")
      (node (ref "C1") (pin "1") (pinfunction "1_1") (pintype "passive"))
      (node (ref "C10") (pin "1") (pinfunction "1_1") (pintype "passive"))
      (node (ref "C11") (pin "1") (pinfunction "1_1") (pintype "passive"))
      (node (ref "C12") (pin "1") (pinfunction "1_1") (pintype "passive"))
      (node (ref "C2") (pin "1") (pinfunction "1_1") (pintype "passive"))
      (node (ref "C3") (pin "1") (pinfunction "1_1") (pintype "passive"))
      (node (ref "C4") (pin "1") (pinfunction "1_1") (pintype "passive"))
      (node (ref "C5") (pin "1") (pinfunction "1_1") (pintype "passive"))
      (node (ref "C7") (pin "1") (pinfunction "1_1") (pintype "passive"))
      (node (ref "C8") (pin "1") (pinfunction "1_1") (pintype "passive"))
      (node (ref "C9") (pin "1") (pinfunction "1_1") (pintype "passive"))
      (node (ref "D1") (pin "1") (pinfunction "A_1") (pintype "passive"))
      (node (ref "D2") (pin "K") (pinfunction "K_K") (pintype "passive"))
      (node (ref "D6") (pin "K") (pinfunction "K_K") (pintype "passive"))
      (node (ref "D8") (pin "2") (pinfunction "2_2") (pintype "passive"))
      (node (ref "ISO1") (pin "5") (pinfunction "BGND_5") (pintype "passive"))
      (node (ref "J4") (pin "1") (pintype "passive"))
      (node (ref "J6") (pin "1") (pintype "passive"))
      (node (ref "J8") (pin "2") (pinfunction "2_2") (pintype "passive"))
      (node (ref "Q2") (pin "2") (pinfunction "S_2") (pintype "passive"))
      (node (ref "Q3") (pin "2") (pinfunction "S_2") (pintype "passive"))
      (node (ref "Q4") (pin "2") (pinfunction "S_2") (pintype "passive"))
      (node (ref "Q5") (pin "2") (pinfunction "S_2") (pintype "passive"))
      (node (ref "R11") (pin "1") (pinfunction "1_1") (pintype "passive"))
      (node (ref "R12") (pin "1") (pinfunction "1_1") (pintype "passive"))
      (node (ref "R13") (pin "1") (pinfunction "1_1") (pintype "passive"))
      (node (ref "R14") (pin "1") (pinfunction "1_1") (pintype "passive"))
      (node (ref "R21") (pin "1") (pinfunction "1_1") (pintype "passive"))
      (node (ref "R24") (pin "1") (pinfunction "1_1") (pintype "passive"))
      (node (ref "R3") (pin "1") (pinfunction "1_1") (pintype "passive"))
      (node (ref "TP1") (pin "1") (pinfunction "1_1") (pintype "passive"))
      (node (ref "U1") (pin "2") (pinfunction "GND_2") (pintype "passive"))
      (node (ref "U2") (pin "2") (pinfunction "GND_2") (pintype "passive"))
      (node (ref "U3") (pin "2") (pinfunction "GND_2") (pintype "passive"))
    )
    (net (code "13") (name "GND_EXT") (class "Default")
      (node (ref "C11") (pin "2") (pinfunction "2_2") (pintype "passive"))
      (node (ref "C6") (pin "1") (pinfunction "1_1") (pintype "passive"))
      (node (ref "D3") (pin "2") (pinfunction "2_2") (pintype "passive"))
      (node (ref "D4") (pin "3") (pinfunction "A_3") (pintype "passive"))
      (node (ref "ISO1") (pin "4") (pinfunction "AGND_4") (pintype "passive"))
      (node (ref "J7") (pin "4") (pinfunction "4_4") (pintype "passive"))
      (node (ref "TP2") (pin "1") (pinfunction "1_1") (pintype "passive"))
    )
    (net (code "14") (name "Net-(D2-PadA)") (class "Default")
      (node (ref "D2") (pin "A") (pinfunction "A_A") (pintype "passive"))
      (node (ref "R15") (pin "2") (pinfunction "2_2") (pintype "passive"))
    )
    (net (code "15") (name "Net-(D6-PadA)") (class "Default")
      (node (ref "D6") (pin "A") (pinfunction "A_A") (pintype "passive"))
      (node (ref "R22") (pin "2") (pinfunction "2_2") (pintype "passive"))
    )
    (net (code "16") (name "Net-(J8-Pad1)") (class "Default")
      (node (ref "J8") (pin "1") (pinfunction "1_1") (pintype "passive"))
      (node (ref "R23") (pin "2") (pinfunction "2_2") (pintype "passive"))
    )
    (net (code "17") (name "Net-(Q2-G)") (class "Default")
      (node (ref "Q2") (pin "1") (pinfunction "G_1") (pintype "passive"))
      (node (ref "Q3") (pin "3") (pinfunction "D_3") (pintype "passive"))
      (node (ref "R5") (pin "1") (pinfunction "1_1") (pintype "passive"))
    )
    (net (code "18") (name "Net-(Q3-G)") (class "Default")
      (node (ref "C12") (pin "2") (pinfunction "2_2") (pintype "passive"))
      (node (ref "Q3") (pin "1") (pinfunction "G_1") (pintype "passive"))
      (node (ref "R24") (pin "2") (pinfunction "2_2") (pintype "passive"))
      (node (ref "R4") (pin "1") (pinfunction "1_1") (pintype "passive"))
    )
    (net (code "19") (name "Net-(U2-INA+)") (class "Default")
      (node (ref "C5") (pin "2") (pinfunction "2_2") (pintype "passive"))
      (node (ref "R11") (pin "2") (pinfunction "2_2") (pintype "passive"))
      (node (ref "R14") (pin "2") (pinfunction "2_2") (pintype "passive"))
      (node (ref "R9") (pin "1") (pinfunction "1_1") (pintype "passive"))
      (node (ref "U2") (pin "3") (pinfunction "INA+_3") (pintype "passive"))
    )
    (net (code "20") (name "Net-(U2-INB-)") (class "Default")
      (node (ref "C4") (pin "2") (pinfunction "2_2") (pintype "passive"))
      (node (ref "R12") (pin "2") (pinfunction "2_2") (pintype "passive"))
      (node (ref "R13") (pin "2") (pinfunction "2_2") (pintype "passive"))
      (node (ref "R8") (pin "1") (pinfunction "1_1") (pintype "passive"))
      (node (ref "U2") (pin "4") (pinfunction "INB-_4") (pintype "passive"))
    )
    (net (code "21") (name "Net-(U3-AIN)") (class "Default")
      (node (ref "R20") (pin "1") (pinfunction "1_1") (pintype "passive"))
      (node (ref "R21") (pin "2") (pinfunction "2_2") (pintype "passive"))
      (node (ref "U3") (pin "3") (pinfunction "AIN_3") (pintype "passive"))
    )
    (net (code "22") (name "VBAT") (class "Default")
      (node (ref "D1") (pin "2") (pinfunction "K_2") (pintype "passive"))
      (node (ref "FH2") (pin "1") (pinfunction "1_1") (pintype "passive"))
      (node (ref "Q1") (pin "2") (pinfunction "S_2") (pintype "passive"))
      (node (ref "R1") (pin "2") (pinfunction "2_2") (pintype "passive"))
      (node (ref "R4") (pin "2") (pinfunction "2_2") (pintype "passive"))
      (node (ref "R5") (pin "2") (pinfunction "2_2") (pintype "passive"))
    )
    (net (code "23") (name "VBAT_CTRL") (class "Default")
      (node (ref "C1") (pin "2") (pinfunction "2_2") (pintype "passive"))
      (node (ref "J1") (pin "1") (pintype "passive"))
      (node (ref "J3") (pin "1") (pintype "passive"))
      (node (ref "Q1") (pin "3") (pinfunction "D_3") (pintype "passive"))
      (node (ref "R20") (pin "2") (pinfunction "2_2") (pintype "passive"))
      (node (ref "R8") (pin "2") (pinfunction "2_2") (pintype "passive"))
      (node (ref "R9") (pin "2") (pinfunction "2_2") (pintype "passive"))
      (node (ref "U1") (pin "1") (pinfunction "VIN_1") (pintype "passive"))
    )
    (net (code "24") (name "VBAT_IN") (class "Default")
      (node (ref "FH1") (pin "1") (pinfunction "1_1") (pintype "passive"))
      (node (ref "J2") (pin "1") (pintype "passive"))
    )
    (net (code "25") (name "VCC_EXT") (class "Default")
      (node (ref "C6") (pin "2") (pinfunction "2_2") (pintype "passive"))
      (node (ref "D3") (pin "1") (pinfunction "1_1") (pintype "passive"))
      (node (ref "ISO1") (pin "1") (pinfunction "AVDD_1") (pintype "passive"))
      (node (ref "J7") (pin "1") (pinfunction "1_1") (pintype "passive"))
      (node (ref "R16") (pin "2") (pinfunction "2_2") (pintype "passive"))
      (node (ref "R17") (pin "2") (pinfunction "2_2") (pintype "passive"))
    )
    (net (code "26") (name "unconnected-(MTH1-Pad1)") (class "Default")
      (node (ref "MTH1") (pin "1") (pinfunction "1_1") (pintype "passive+no_connect"))
    )
    (net (code "27") (name "unconnected-(MTH2-Pad1)") (class "Default")
      (node (ref "MTH2") (pin "1") (pinfunction "1_1") (pintype "passive+no_connect"))
    )
    (net (code "28") (name "unconnected-(MTH3-Pad1)") (class "Default")
      (node (ref "MTH3") (pin "1") (pinfunction "1_1") (pintype "passive+no_connect"))
    )
    (net (code "29") (name "unconnected-(MTH4-Pad1)") (class "Default")
      (node (ref "MTH4") (pin "1") (pinfunction "1_1") (pintype "passive+no_connect"))
    )
    (net (code "30") (name "unconnected-(R11-Pad3)") (class "Default")
      (node (ref "R11") (pin "3") (pinfunction "3_3") (pintype "passive+no_connect"))
    )
    (net (code "31") (name "unconnected-(R12-Pad3)") (class "Default")
      (node (ref "R12") (pin "3") (pinfunction "3_3") (pintype "passive+no_connect"))
    )
    (net (code "32") (name "unconnected-(U1-EN-Pad4)") (class "Default")
      (node (ref "U1") (pin "4") (pinfunction "EN_4") (pintype "passive+no_connect"))
    )
  )
)
